# 32_ch_sample_and_hold.net
KiCad netlist of a schematic drawn in EAGLE
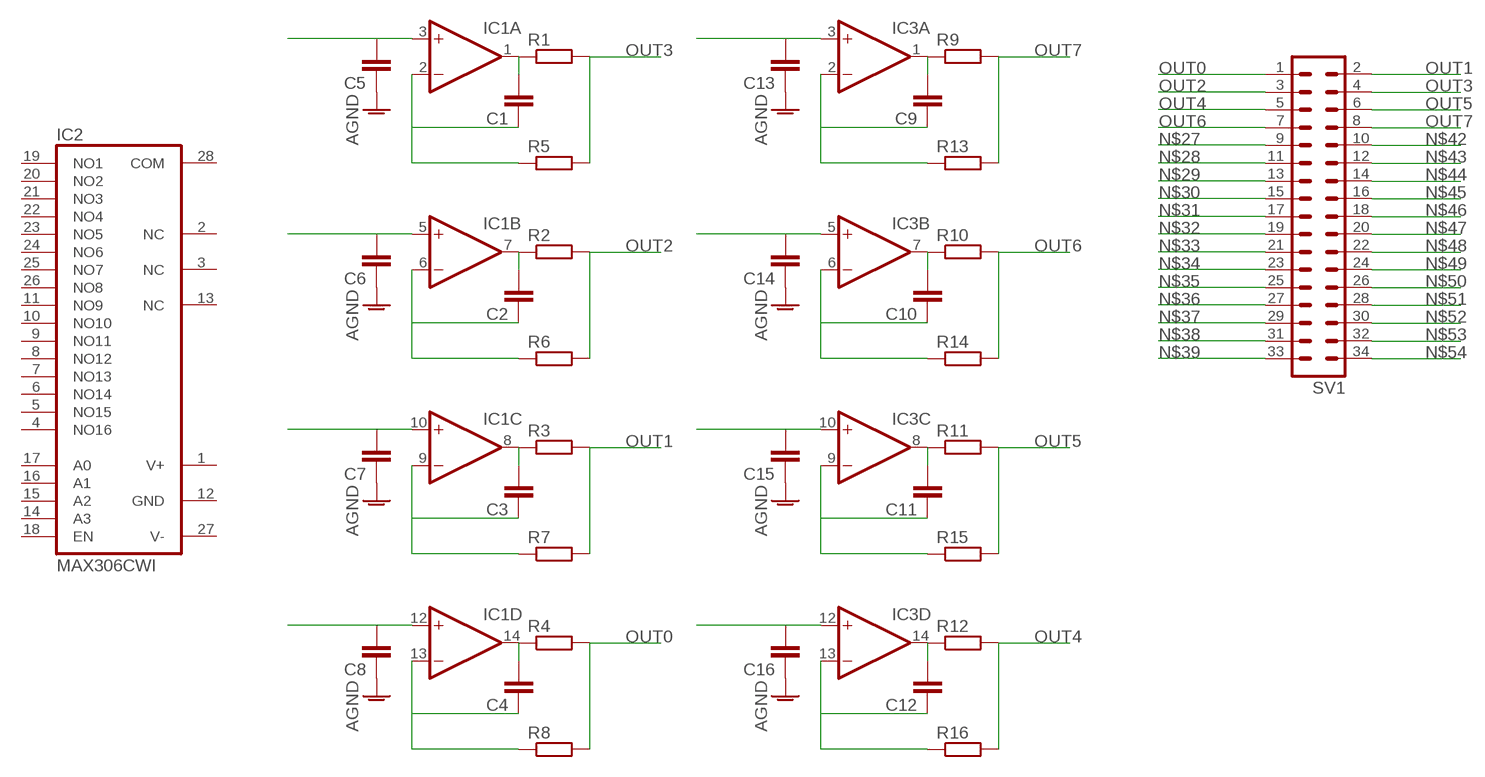
[diagram p0: schematic, sheet 1]

(export (version "E")
  (design (tool "Eeschema 10.0.6"))
  (components
    (comp (ref "C1")
      (value "C-EUC0603")
      (footprint "eagle-import:C0603")
      (libsource (lib "eagle-import") (part "C-EUC0603"))
    )
    (comp (ref "C2")
      (value "C-EUC0603")
      (footprint "eagle-import:C0603")
      (libsource (lib "eagle-import") (part "C-EUC0603"))
    )
    (comp (ref "C3")
      (value "C-EUC0603")
      (footprint "eagle-import:C0603")
      (libsource (lib "eagle-import") (part "C-EUC0603"))
    )
    (comp (ref "C4")
      (value "C-EUC0603")
      (footprint "eagle-import:C0603")
      (libsource (lib "eagle-import") (part "C-EUC0603"))
    )
    (comp (ref "C5")
      (value "C-EUC1206")
      (footprint "eagle-import:C1206")
      (libsource (lib "eagle-import") (part "C-EUC1206"))
    )
    (comp (ref "C6")
      (value "C-EUC1206")
      (footprint "eagle-import:C1206")
      (libsource (lib "eagle-import") (part "C-EUC1206"))
    )
    (comp (ref "C7")
      (value "C-EUC1206")
      (footprint "eagle-import:C1206")
      (libsource (lib "eagle-import") (part "C-EUC1206"))
    )
    (comp (ref "C8")
      (value "C-EUC1206")
      (footprint "eagle-import:C1206")
      (libsource (lib "eagle-import") (part "C-EUC1206"))
    )
    (comp (ref "C9")
      (value "C-EUC0603")
      (footprint "eagle-import:C0603")
      (libsource (lib "eagle-import") (part "C-EUC0603"))
    )
    (comp (ref "C10")
      (value "C-EUC0603")
      (footprint "eagle-import:C0603")
      (libsource (lib "eagle-import") (part "C-EUC0603"))
    )
    (comp (ref "C11")
      (value "C-EUC0603")
      (footprint "eagle-import:C0603")
      (libsource (lib "eagle-import") (part "C-EUC0603"))
    )
    (comp (ref "C12")
      (value "C-EUC0603")
      (footprint "eagle-import:C0603")
      (libsource (lib "eagle-import") (part "C-EUC0603"))
    )
    (comp (ref "C13")
      (value "C-EUC1206")
      (footprint "eagle-import:C1206")
      (libsource (lib "eagle-import") (part "C-EUC1206"))
    )
    (comp (ref "C14")
      (value "C-EUC1206")
      (footprint "eagle-import:C1206")
      (libsource (lib "eagle-import") (part "C-EUC1206"))
    )
    (comp (ref "C15")
      (value "C-EUC1206")
      (footprint "eagle-import:C1206")
      (libsource (lib "eagle-import") (part "C-EUC1206"))
    )
    (comp (ref "C16")
      (value "C-EUC1206")
      (footprint "eagle-import:C1206")
      (libsource (lib "eagle-import") (part "C-EUC1206"))
    )
    (comp (ref "IC1")
      (value "TL074D")
      (footprint "eagle-import:SO14")
      (libsource (lib "eagle-import") (part "TL074D"))
    )
    (comp (ref "IC2")
      (value "MAX306CWI")
      (footprint "eagle-import:SO28L")
      (fields (field (name "MF") "MAXIM"))
      (libsource (lib "eagle-import") (part "MAX306CWI"))
    )
    (comp (ref "IC3")
      (value "TL074D")
      (footprint "eagle-import:SO14")
      (libsource (lib "eagle-import") (part "TL074D"))
    )
    (comp (ref "R1")
      (value "R-EU_R0603")
      (footprint "eagle-import:R0603")
      (libsource (lib "eagle-import") (part "R-EU_R0603"))
    )
    (comp (ref "R2")
      (value "R-EU_R0603")
      (footprint "eagle-import:R0603")
      (libsource (lib "eagle-import") (part "R-EU_R0603"))
    )
    (comp (ref "R3")
      (value "R-EU_R0603")
      (footprint "eagle-import:R0603")
      (libsource (lib "eagle-import") (part "R-EU_R0603"))
    )
    (comp (ref "R4")
      (value "R-EU_R0603")
      (footprint "eagle-import:R0603")
      (libsource (lib "eagle-import") (part "R-EU_R0603"))
    )
    (comp (ref "R5")
      (value "R-EU_R0603")
      (footprint "eagle-import:R0603")
      (libsource (lib "eagle-import") (part "R-EU_R0603"))
    )
    (comp (ref "R6")
      (value "R-EU_R0603")
      (footprint "eagle-import:R0603")
      (libsource (lib "eagle-import") (part "R-EU_R0603"))
    )
    (comp (ref "R7")
      (value "R-EU_R0603")
      (footprint "eagle-import:R0603")
      (libsource (lib "eagle-import") (part "R-EU_R0603"))
    )
    (comp (ref "R8")
      (value "R-EU_R0603")
      (footprint "eagle-import:R0603")
      (libsource (lib "eagle-import") (part "R-EU_R0603"))
    )
    (comp (ref "R9")
      (value "R-EU_R0603")
      (footprint "eagle-import:R0603")
      (libsource (lib "eagle-import") (part "R-EU_R0603"))
    )
    (comp (ref "R10")
      (value "R-EU_R0603")
      (footprint "eagle-import:R0603")
      (libsource (lib "eagle-import") (part "R-EU_R0603"))
    )
    (comp (ref "R11")
      (value "R-EU_R0603")
      (footprint "eagle-import:R0603")
      (libsource (lib "eagle-import") (part "R-EU_R0603"))
    )
    (comp (ref "R12")
      (value "R-EU_R0603")
      (footprint "eagle-import:R0603")
      (libsource (lib "eagle-import") (part "R-EU_R0603"))
    )
    (comp (ref "R13")
      (value "R-EU_R0603")
      (footprint "eagle-import:R0603")
      (libsource (lib "eagle-import") (part "R-EU_R0603"))
    )
    (comp (ref "R14")
      (value "R-EU_R0603")
      (footprint "eagle-import:R0603")
      (libsource (lib "eagle-import") (part "R-EU_R0603"))
    )
    (comp (ref "R15")
      (value "R-EU_R0603")
      (footprint "eagle-import:R0603")
      (libsource (lib "eagle-import") (part "R-EU_R0603"))
    )
    (comp (ref "R16")
      (value "R-EU_R0603")
      (footprint "eagle-import:R0603")
      (libsource (lib "eagle-import") (part "R-EU_R0603"))
    )
    (comp (ref "SV1")
      (value "MA17-2")
      (footprint "eagle-import:MA17-2")
      (libsource (lib "eagle-import") (part "MA17-2"))
    )
  )
  (nets
    (net (code "1") (name "/GND") (class "Default")
      (node (ref "IC2") (pin "12") (pinfunction "GND_12") (pintype "power_in"))
    )
    (net (code "2") (name "/N$27") (class "Default")
      (node (ref "SV1") (pin "9") (pinfunction "9_9") (pintype "passive"))
    )
    (net (code "3") (name "/N$28") (class "Default")
      (node (ref "SV1") (pin "11") (pinfunction "11_11") (pintype "passive"))
    )
    (net (code "4") (name "/N$29") (class "Default")
      (node (ref "SV1") (pin "13") (pinfunction "13_13") (pintype "passive"))
    )
    (net (code "5") (name "/N$30") (class "Default")
      (node (ref "SV1") (pin "15") (pinfunction "15_15") (pintype "passive"))
    )
    (net (code "6") (name "/N$31") (class "Default")
      (node (ref "SV1") (pin "17") (pinfunction "17_17") (pintype "passive"))
    )
    (net (code "7") (name "/N$32") (class "Default")
      (node (ref "SV1") (pin "19") (pinfunction "19_19") (pintype "passive"))
    )
    (net (code "8") (name "/N$33") (class "Default")
      (node (ref "SV1") (pin "21") (pinfunction "21_21") (pintype "passive"))
    )
    (net (code "9") (name "/N$34") (class "Default")
      (node (ref "SV1") (pin "23") (pinfunction "23_23") (pintype "passive"))
    )
    (net (code "10") (name "/N$35") (class "Default")
      (node (ref "SV1") (pin "25") (pinfunction "25_25") (pintype "passive"))
    )
    (net (code "11") (name "/N$36") (class "Default")
      (node (ref "SV1") (pin "27") (pinfunction "27_27") (pintype "passive"))
    )
    (net (code "12") (name "/N$37") (class "Default")
      (node (ref "SV1") (pin "29") (pinfunction "29_29") (pintype "passive"))
    )
    (net (code "13") (name "/N$38") (class "Default")
      (node (ref "SV1") (pin "31") (pinfunction "31_31") (pintype "passive"))
    )
    (net (code "14") (name "/N$39") (class "Default")
      (node (ref "SV1") (pin "33") (pinfunction "33_33") (pintype "passive"))
    )
    (net (code "15") (name "/N$42") (class "Default")
      (node (ref "SV1") (pin "10") (pinfunction "10_10") (pintype "passive"))
    )
    (net (code "16") (name "/N$43") (class "Default")
      (node (ref "SV1") (pin "12") (pinfunction "12_12") (pintype "passive"))
    )
    (net (code "17") (name "/N$44") (class "Default")
      (node (ref "SV1") (pin "14") (pinfunction "14_14") (pintype "passive"))
    )
    (net (code "18") (name "/N$45") (class "Default")
      (node (ref "SV1") (pin "16") (pinfunction "16_16") (pintype "passive"))
    )
    (net (code "19") (name "/N$46") (class "Default")
      (node (ref "SV1") (pin "18") (pinfunction "18_18") (pintype "passive"))
    )
    (net (code "20") (name "/N$47") (class "Default")
      (node (ref "SV1") (pin "20") (pinfunction "20_20") (pintype "passive"))
    )
    (net (code "21") (name "/N$48") (class "Default")
      (node (ref "SV1") (pin "22") (pinfunction "22_22") (pintype "passive"))
    )
    (net (code "22") (name "/N$49") (class "Default")
      (node (ref "SV1") (pin "24") (pinfunction "24_24") (pintype "passive"))
    )
    (net (code "23") (name "/N$50") (class "Default")
      (node (ref "SV1") (pin "26") (pinfunction "26_26") (pintype "passive"))
    )
    (net (code "24") (name "/N$51") (class "Default")
      (node (ref "SV1") (pin "28") (pinfunction "28_28") (pintype "passive"))
    )
    (net (code "25") (name "/N$52") (class "Default")
      (node (ref "SV1") (pin "30") (pinfunction "30_30") (pintype "passive"))
    )
    (net (code "26") (name "/N$53") (class "Default")
      (node (ref "SV1") (pin "32") (pinfunction "32_32") (pintype "passive"))
    )
    (net (code "27") (name "/N$54") (class "Default")
      (node (ref "SV1") (pin "34") (pinfunction "34_34") (pintype "passive"))
    )
    (net (code "28") (name "/OUT0") (class "Default")
      (node (ref "R4") (pin "2") (pinfunction "2_2") (pintype "passive"))
      (node (ref "R8") (pin "2") (pinfunction "2_2") (pintype "passive"))
      (node (ref "SV1") (pin "1") (pinfunction "1_1") (pintype "passive"))
    )
    (net (code "29") (name "/OUT1") (class "Default")
      (node (ref "R3") (pin "2") (pinfunction "2_2") (pintype "passive"))
      (node (ref "R7") (pin "2") (pinfunction "2_2") (pintype "passive"))
      (node (ref "SV1") (pin "2") (pinfunction "2_2") (pintype "passive"))
    )
    (net (code "30") (name "/OUT2") (class "Default")
      (node (ref "R2") (pin "2") (pinfunction "2_2") (pintype "passive"))
      (node (ref "R6") (pin "2") (pinfunction "2_2") (pintype "passive"))
      (node (ref "SV1") (pin "3") (pinfunction "3_3") (pintype "passive"))
    )
    (net (code "31") (name "/OUT3") (class "Default")
      (node (ref "R1") (pin "2") (pinfunction "2_2") (pintype "passive"))
      (node (ref "R5") (pin "2") (pinfunction "2_2") (pintype "passive"))
      (node (ref "SV1") (pin "4") (pinfunction "4_4") (pintype "passive"))
    )
    (net (code "32") (name "/OUT4") (class "Default")
      (node (ref "R12") (pin "2") (pinfunction "2_2") (pintype "passive"))
      (node (ref "R16") (pin "2") (pinfunction "2_2") (pintype "passive"))
      (node (ref "SV1") (pin "5") (pinfunction "5_5") (pintype "passive"))
    )
    (net (code "33") (name "/OUT5") (class "Default")
      (node (ref "R11") (pin "2") (pinfunction "2_2") (pintype "passive"))
      (node (ref "R15") (pin "2") (pinfunction "2_2") (pintype "passive"))
      (node (ref "SV1") (pin "6") (pinfunction "6_6") (pintype "passive"))
    )
    (net (code "34") (name "/OUT6") (class "Default")
      (node (ref "R10") (pin "2") (pinfunction "2_2") (pintype "passive"))
      (node (ref "R14") (pin "2") (pinfunction "2_2") (pintype "passive"))
      (node (ref "SV1") (pin "7") (pinfunction "7_7") (pintype "passive"))
    )
    (net (code "35") (name "/OUT7") (class "Default")
      (node (ref "R13") (pin "2") (pinfunction "2_2") (pintype "passive"))
      (node (ref "R9") (pin "2") (pinfunction "2_2") (pintype "passive"))
      (node (ref "SV1") (pin "8") (pinfunction "8_8") (pintype "passive"))
    )
    (net (code "36") (name "/V+") (class "Default")
      (node (ref "IC2") (pin "1") (pinfunction "V+_1") (pintype "power_in"))
    )
    (net (code "37") (name "/V-") (class "Default")
      (node (ref "IC2") (pin "27") (pinfunction "V-_27") (pintype "power_in"))
    )
    (net (code "38") (name "AGND") (class "Default")
      (node (ref "C13") (pin "1") (pinfunction "1_1") (pintype "passive"))
      (node (ref "C14") (pin "1") (pinfunction "1_1") (pintype "passive"))
      (node (ref "C15") (pin "1") (pinfunction "1_1") (pintype "passive"))
      (node (ref "C16") (pin "1") (pinfunction "1_1") (pintype "passive"))
      (node (ref "C5") (pin "1") (pinfunction "1_1") (pintype "passive"))
      (node (ref "C6") (pin "1") (pinfunction "1_1") (pintype "passive"))
      (node (ref "C7") (pin "1") (pinfunction "1_1") (pintype "passive"))
      (node (ref "C8") (pin "1") (pinfunction "1_1") (pintype "passive"))
    )
    (net (code "39") (name "Net-(IC1A-+IN)") (class "Default")
      (node (ref "C5") (pin "2") (pinfunction "2_2") (pintype "passive"))
      (node (ref "IC1") (pin "3") (pinfunction "+IN_3") (pintype "input"))
    )
    (net (code "40") (name "Net-(IC1A--IN)") (class "Default")
      (node (ref "C1") (pin "1") (pinfunction "1_1") (pintype "passive"))
      (node (ref "IC1") (pin "2") (pinfunction "-IN_2") (pintype "input"))
      (node (ref "R5") (pin "1") (pinfunction "1_1") (pintype "passive"))
    )
    (net (code "41") (name "Net-(IC1A-OUT)") (class "Default")
      (node (ref "C1") (pin "2") (pinfunction "2_2") (pintype "passive"))
      (node (ref "IC1") (pin "1") (pinfunction "OUT_1") (pintype "output"))
      (node (ref "R1") (pin "1") (pinfunction "1_1") (pintype "passive"))
    )
    (net (code "42") (name "Net-(IC1B-+IN)") (class "Default")
      (node (ref "C6") (pin "2") (pinfunction "2_2") (pintype "passive"))
      (node (ref "IC1") (pin "5") (pinfunction "+IN_5") (pintype "input"))
    )
    (net (code "43") (name "Net-(IC1B--IN)") (class "Default")
      (node (ref "C2") (pin "1") (pinfunction "1_1") (pintype "passive"))
      (node (ref "IC1") (pin "6") (pinfunction "-IN_6") (pintype "input"))
      (node (ref "R6") (pin "1") (pinfunction "1_1") (pintype "passive"))
    )
    (net (code "44") (name "Net-(IC1B-OUT)") (class "Default")
      (node (ref "C2") (pin "2") (pinfunction "2_2") (pintype "passive"))
      (node (ref "IC1") (pin "7") (pinfunction "OUT_7") (pintype "output"))
      (node (ref "R2") (pin "1") (pinfunction "1_1") (pintype "passive"))
    )
    (net (code "45") (name "Net-(IC1C-+IN)") (class "Default")
      (node (ref "C7") (pin "2") (pinfunction "2_2") (pintype "passive"))
      (node (ref "IC1") (pin "10") (pinfunction "+IN_10") (pintype "input"))
    )
    (net (code "46") (name "Net-(IC1C--IN)") (class "Default")
      (node (ref "C3") (pin "1") (pinfunction "1_1") (pintype "passive"))
      (node (ref "IC1") (pin "9") (pinfunction "-IN_9") (pintype "input"))
      (node (ref "R7") (pin "1") (pinfunction "1_1") (pintype "passive"))
    )
    (net (code "47") (name "Net-(IC1C-OUT)") (class "Default")
      (node (ref "C3") (pin "2") (pinfunction "2_2") (pintype "passive"))
      (node (ref "IC1") (pin "8") (pinfunction "OUT_8") (pintype "output"))
      (node (ref "R3") (pin "1") (pinfunction "1_1") (pintype "passive"))
    )
    (net (code "48") (name "Net-(IC1D-+IN)") (class "Default")
      (node (ref "C8") (pin "2") (pinfunction "2_2") (pintype "passive"))
      (node (ref "IC1") (pin "12") (pinfunction "+IN_12") (pintype "input"))
    )
    (net (code "49") (name "Net-(IC1D--IN)") (class "Default")
      (node (ref "C4") (pin "1") (pinfunction "1_1") (pintype "passive"))
      (node (ref "IC1") (pin "13") (pinfunction "-IN_13") (pintype "input"))
      (node (ref "R8") (pin "1") (pinfunction "1_1") (pintype "passive"))
    )
    (net (code "50") (name "Net-(IC1D-OUT)") (class "Default")
      (node (ref "C4") (pin "2") (pinfunction "2_2") (pintype "passive"))
      (node (ref "IC1") (pin "14") (pinfunction "OUT_14") (pintype "output"))
      (node (ref "R4") (pin "1") (pinfunction "1_1") (pintype "passive"))
    )
    (net (code "51") (name "Net-(IC3A-+IN)") (class "Default")
      (node (ref "C13") (pin "2") (pinfunction "2_2") (pintype "passive"))
      (node (ref "IC3") (pin "3") (pinfunction "+IN_3") (pintype "input"))
    )
    (net (code "52") (name "Net-(IC3A--IN)") (class "Default")
      (node (ref "C9") (pin "1") (pinfunction "1_1") (pintype "passive"))
      (node (ref "IC3") (pin "2") (pinfunction "-IN_2") (pintype "input"))
      (node (ref "R13") (pin "1") (pinfunction "1_1") (pintype "passive"))
    )
    (net (code "53") (name "Net-(IC3A-OUT)") (class "Default")
      (node (ref "C9") (pin "2") (pinfunction "2_2") (pintype "passive"))
      (node (ref "IC3") (pin "1") (pinfunction "OUT_1") (pintype "output"))
      (node (ref "R9") (pin "1") (pinfunction "1_1") (pintype "passive"))
    )
    (net (code "54") (name "Net-(IC3B-+IN)") (class "Default")
      (node (ref "C14") (pin "2") (pinfunction "2_2") (pintype "passive"))
      (node (ref "IC3") (pin "5") (pinfunction "+IN_5") (pintype "input"))
    )
    (net (code "55") (name "Net-(IC3B--IN)") (class "Default")
      (node (ref "C10") (pin "1") (pinfunction "1_1") (pintype "passive"))
      (node (ref "IC3") (pin "6") (pinfunction "-IN_6") (pintype "input"))
      (node (ref "R14") (pin "1") (pinfunction "1_1") (pintype "passive"))
    )
    (net (code "56") (name "Net-(IC3B-OUT)") (class "Default")
      (node (ref "C10") (pin "2") (pinfunction "2_2") (pintype "passive"))
      (node (ref "IC3") (pin "7") (pinfunction "OUT_7") (pintype "output"))
      (node (ref "R10") (pin "1") (pinfunction "1_1") (pintype "passive"))
    )
    (net (code "57") (name "Net-(IC3C-+IN)") (class "Default")
      (node (ref "C15") (pin "2") (pinfunction "2_2") (pintype "passive"))
      (node (ref "IC3") (pin "10") (pinfunction "+IN_10") (pintype "input"))
    )
    (net (code "58") (name "Net-(IC3C--IN)") (class "Default")
      (node (ref "C11") (pin "1") (pinfunction "1_1") (pintype "passive"))
      (node (ref "IC3") (pin "9") (pinfunction "-IN_9") (pintype "input"))
      (node (ref "R15") (pin "1") (pinfunction "1_1") (pintype "passive"))
    )
    (net (code "59") (name "Net-(IC3C-OUT)") (class "Default")
      (node (ref "C11") (pin "2") (pinfunction "2_2") (pintype "passive"))
      (node (ref "IC3") (pin "8") (pinfunction "OUT_8") (pintype "output"))
      (node (ref "R11") (pin "1") (pinfunction "1_1") (pintype "passive"))
    )
    (net (code "60") (name "Net-(IC3D-+IN)") (class "Default")
      (node (ref "C16") (pin "2") (pinfunction "2_2") (pintype "passive"))
      (node (ref "IC3") (pin "12") (pinfunction "+IN_12") (pintype "input"))
    )
    (net (code "61") (name "Net-(IC3D--IN)") (class "Default")
      (node (ref "C12") (pin "1") (pinfunction "1_1") (pintype "passive"))
      (node (ref "IC3") (pin "13") (pinfunction "-IN_13") (pintype "input"))
      (node (ref "R16") (pin "1") (pinfunction "1_1") (pintype "passive"))
    )
    (net (code "62") (name "Net-(IC3D-OUT)") (class "Default")
      (node (ref "C12") (pin "2") (pinfunction "2_2") (pintype "passive"))
      (node (ref "IC3") (pin "14") (pinfunction "OUT_14") (pintype "output"))
      (node (ref "R12") (pin "1") (pinfunction "1_1") (pintype "passive"))
    )
    (net (code "63") (name "unconnected-(IC2-A0-Pad17)") (class "Default")
      (node (ref "IC2") (pin "17") (pinfunction "A0_17") (pintype "input"))
    )
    (net (code "64") (name "unconnected-(IC2-A1-Pad16)") (class "Default")
      (node (ref "IC2") (pin "16") (pinfunction "A1_16") (pintype "input"))
    )
    (net (code "65") (name "unconnected-(IC2-A2-Pad15)") (class "Default")
      (node (ref "IC2") (pin "15") (pinfunction "A2_15") (pintype "input"))
    )
    (net (code "66") (name "unconnected-(IC2-A3-Pad14)") (class "Default")
      (node (ref "IC2") (pin "14") (pinfunction "A3_14") (pintype "input"))
    )
    (net (code "67") (name "unconnected-(IC2-COM-Pad28)") (class "Default")
      (node (ref "IC2") (pin "28") (pinfunction "COM_28") (pintype "passive"))
    )
    (net (code "68") (name "unconnected-(IC2-EN-Pad18)") (class "Default")
      (node (ref "IC2") (pin "18") (pinfunction "EN_18") (pintype "input"))
    )
    (net (code "69") (name "unconnected-(IC2-NC-Pad2)") (class "Default")
      (node (ref "IC2") (pin "2") (pinfunction "NC_2") (pintype "no_connect"))
    )
    (net (code "70") (name "unconnected-(IC2-NC-Pad3)") (class "Default")
      (node (ref "IC2") (pin "3") (pinfunction "NC_3") (pintype "no_connect"))
    )
    (net (code "71") (name "unconnected-(IC2-NC-Pad13)") (class "Default")
      (node (ref "IC2") (pin "13") (pinfunction "NC_13") (pintype "no_connect"))
    )
    (net (code "72") (name "unconnected-(IC2-NO1-Pad19)") (class "Default")
      (node (ref "IC2") (pin "19") (pinfunction "NO1_19") (pintype "passive"))
    )
    (net (code "73") (name "unconnected-(IC2-NO2-Pad20)") (class "Default")
      (node (ref "IC2") (pin "20") (pinfunction "NO2_20") (pintype "passive"))
    )
    (net (code "74") (name "unconnected-(IC2-NO3-Pad21)") (class "Default")
      (node (ref "IC2") (pin "21") (pinfunction "NO3_21") (pintype "passive"))
    )
    (net (code "75") (name "unconnected-(IC2-NO4-Pad22)") (class "Default")
      (node (ref "IC2") (pin "22") (pinfunction "NO4_22") (pintype "passive"))
    )
    (net (code "76") (name "unconnected-(IC2-NO5-Pad23)") (class "Default")
      (node (ref "IC2") (pin "23") (pinfunction "NO5_23") (pintype "passive"))
    )
    (net (code "77") (name "unconnected-(IC2-NO6-Pad24)") (class "Default")
      (node (ref "IC2") (pin "24") (pinfunction "NO6_24") (pintype "passive"))
    )
    (net (code "78") (name "unconnected-(IC2-NO7-Pad25)") (class "Default")
      (node (ref "IC2") (pin "25") (pinfunction "NO7_25") (pintype "passive"))
    )
    (net (code "79") (name "unconnected-(IC2-NO8-Pad26)") (class "Default")
      (node (ref "IC2") (pin "26") (pinfunction "NO8_26") (pintype "passive"))
    )
    (net (code "80") (name "unconnected-(IC2-NO9-Pad11)") (class "Default")
      (node (ref "IC2") (pin "11") (pinfunction "NO9_11") (pintype "passive"))
    )
    (net (code "81") (name "unconnected-(IC2-NO10-Pad10)") (class "Default")
      (node (ref "IC2") (pin "10") (pinfunction "NO10_10") (pintype "passive"))
    )
    (net (code "82") (name "unconnected-(IC2-NO11-Pad9)") (class "Default")
      (node (ref "IC2") (pin "9") (pinfunction "NO11_9") (pintype "passive"))
    )
    (net (code "83") (name "unconnected-(IC2-NO12-Pad8)") (class "Default")
      (node (ref "IC2") (pin "8") (pinfunction "NO12_8") (pintype "passive"))
    )
    (net (code "84") (name "unconnected-(IC2-NO13-Pad7)") (class "Default")
      (node (ref "IC2") (pin "7") (pinfunction "NO13_7") (pintype "passive"))
    )
    (net (code "85") (name "unconnected-(IC2-NO14-Pad6)") (class "Default")
      (node (ref "IC2") (pin "6") (pinfunction "NO14_6") (pintype "passive"))
    )
    (net (code "86") (name "unconnected-(IC2-NO15-Pad5)") (class "Default")
      (node (ref "IC2") (pin "5") (pinfunction "NO15_5") (pintype "passive"))
    )
    (net (code "87") (name "unconnected-(IC2-NO16-Pad4)") (class "Default")
      (node (ref "IC2") (pin "4") (pinfunction "NO16_4") (pintype "passive"))
    )
  )
)
